# Power-Supplies.net
KiCad netlist of a schematic drawn in Altium Designer
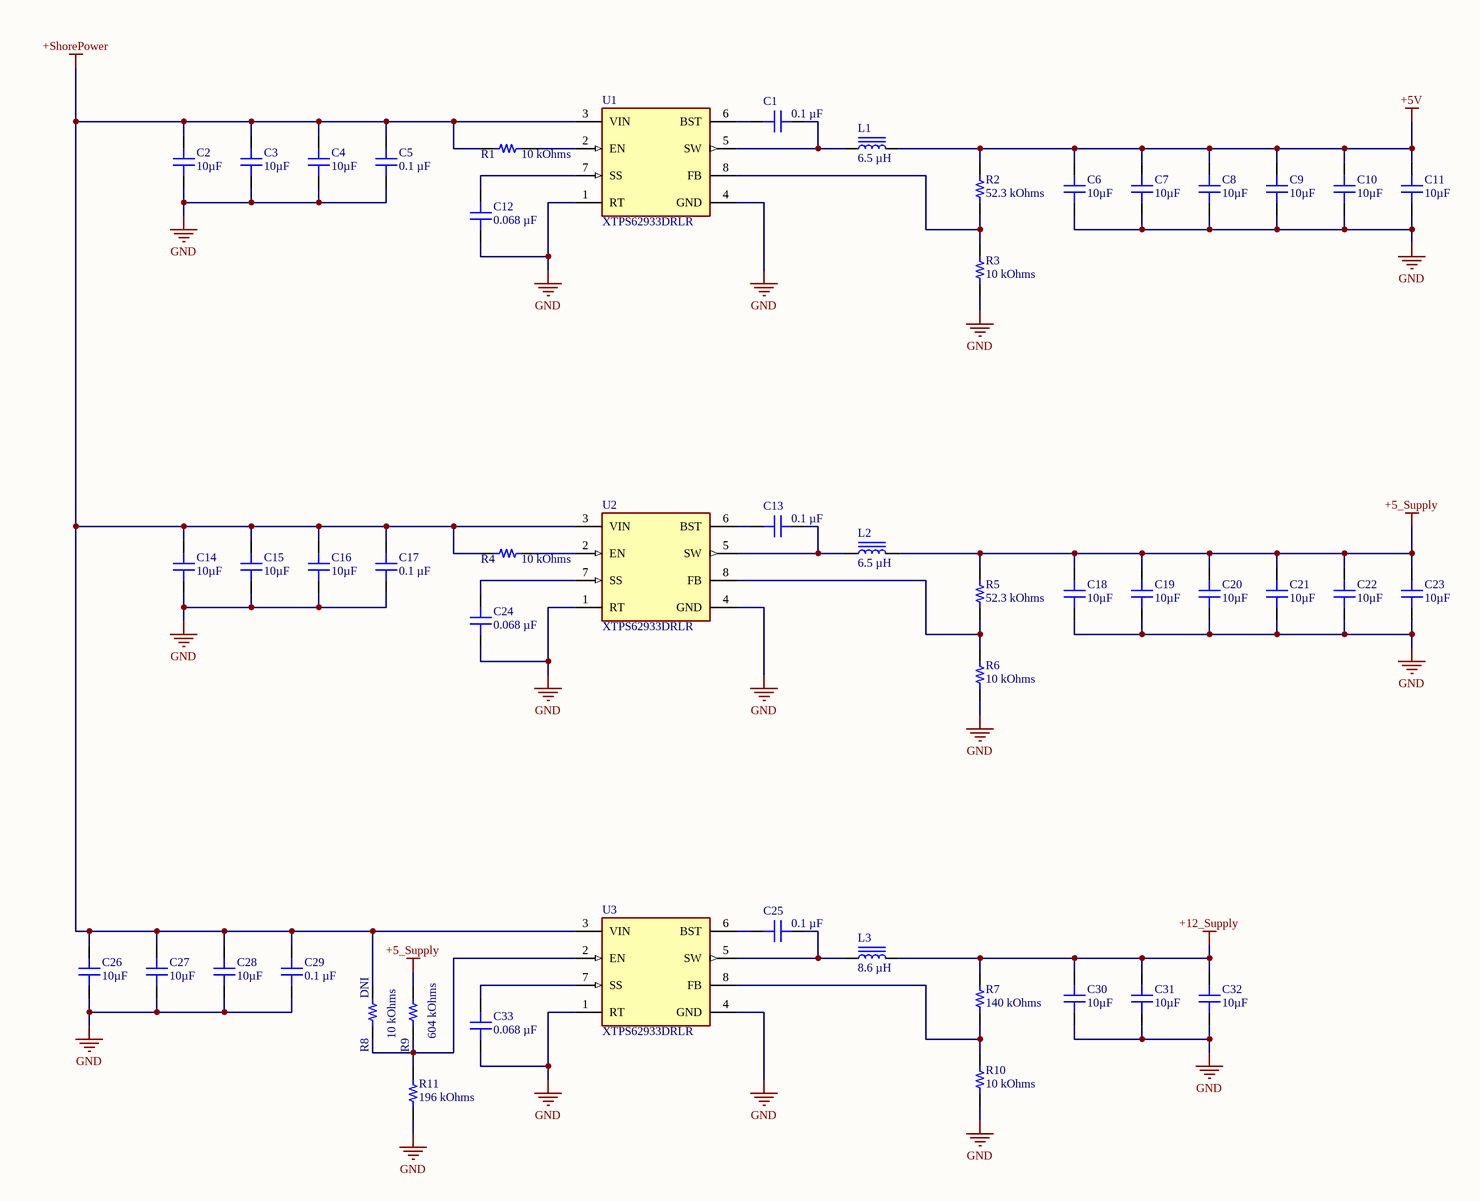
[diagram p0: Power-Supplies.SchDoc]

(export (version "E")
  (design (tool "Eeschema 10.0.6"))
  (components
    (comp (ref "C1")
      (value "0.1 µF")
      (footprint "CAP 0603_1608")
      (description "CAP CER 0.1UF 50V X7R 0603")
      (fields
        (field (name "PART NUMBER") "CL10B104KB8NNWC")
        (field (name "MANUFACTURER") "Samsung Electro-Mechanics")
      )
      (libsource (lib "Celestial Altium Library - altium_library") (part "Capacitor"))
    )
    (comp (ref "C2")
      (value "10µF")
      (footprint "CAP 0805_2012")
      (description "CAP CER 10UF 16V X5R 0805")
      (fields (field (name "PART NUMBER") "CC0805KKX5R7BB106") (field (name "MANUFACTURER") "Yageo"))
      (libsource (lib "Celestial Altium Library - altium_library") (part "Capacitor"))
    )
    (comp (ref "C3")
      (value "10µF")
      (footprint "CAP 0805_2012")
      (description "CAP CER 10UF 16V X5R 0805")
      (fields (field (name "PART NUMBER") "CC0805KKX5R7BB106") (field (name "MANUFACTURER") "Yageo"))
      (libsource (lib "Celestial Altium Library - altium_library") (part "Capacitor"))
    )
    (comp (ref "C4")
      (value "10µF")
      (footprint "CAP 0805_2012")
      (description "CAP CER 10UF 16V X5R 0805")
      (fields (field (name "PART NUMBER") "CC0805KKX5R7BB106") (field (name "MANUFACTURER") "Yageo"))
      (libsource (lib "Celestial Altium Library - altium_library") (part "Capacitor"))
    )
    (comp (ref "C5")
      (value "0.1 µF")
      (footprint "CAP 0603_1608")
      (description "CAP CER 0.1UF 50V X7R 0603")
      (fields
        (field (name "PART NUMBER") "CL10B104KB8NNWC")
        (field (name "MANUFACTURER") "Samsung Electro-Mechanics")
      )
      (libsource (lib "Celestial Altium Library - altium_library") (part "Capacitor"))
    )
    (comp (ref "C6")
      (value "10µF")
      (footprint "CAP 0805_2012")
      (description "CAP CER 10UF 16V X5R 0805")
      (fields (field (name "PART NUMBER") "CC0805KKX5R7BB106") (field (name "MANUFACTURER") "Yageo"))
      (libsource (lib "Celestial Altium Library - altium_library") (part "Capacitor"))
    )
    (comp (ref "C7")
      (value "10µF")
      (footprint "CAP 0805_2012")
      (description "CAP CER 10UF 16V X5R 0805")
      (fields (field (name "PART NUMBER") "CC0805KKX5R7BB106") (field (name "MANUFACTURER") "Yageo"))
      (libsource (lib "Celestial Altium Library - altium_library") (part "Capacitor"))
    )
    (comp (ref "C8")
      (value "10µF")
      (footprint "CAP 0805_2012")
      (description "CAP CER 10UF 16V X5R 0805")
      (fields (field (name "PART NUMBER") "CC0805KKX5R7BB106") (field (name "MANUFACTURER") "Yageo"))
      (libsource (lib "Celestial Altium Library - altium_library") (part "Capacitor"))
    )
    (comp (ref "C9")
      (value "10µF")
      (footprint "CAP 0805_2012")
      (description "CAP CER 10UF 16V X5R 0805")
      (fields (field (name "PART NUMBER") "CC0805KKX5R7BB106") (field (name "MANUFACTURER") "Yageo"))
      (libsource (lib "Celestial Altium Library - altium_library") (part "Capacitor"))
    )
    (comp (ref "C10")
      (value "10µF")
      (footprint "CAP 0805_2012")
      (description "CAP CER 10UF 16V X5R 0805")
      (fields (field (name "PART NUMBER") "CC0805KKX5R7BB106") (field (name "MANUFACTURER") "Yageo"))
      (libsource (lib "Celestial Altium Library - altium_library") (part "Capacitor"))
    )
    (comp (ref "C11")
      (value "10µF")
      (footprint "CAP 0805_2012")
      (description "CAP CER 10UF 16V X5R 0805")
      (fields (field (name "PART NUMBER") "CC0805KKX5R7BB106") (field (name "MANUFACTURER") "Yageo"))
      (libsource (lib "Celestial Altium Library - altium_library") (part "Capacitor"))
    )
    (comp (ref "C12")
      (value "0.068 µF")
      (footprint "CAP 0603_1608")
      (description "CAP CER 0.068UF 25V X7R 0603")
      (fields (field (name "PART NUMBER") "CC0603KRX7R8BB683") (field (name "MANUFACTURER") "Yageo"))
      (libsource (lib "Celestial Altium Library - altium_library") (part "Capacitor"))
    )
    (comp (ref "C13")
      (value "0.1 µF")
      (footprint "CAP 0603_1608")
      (description "CAP CER 0.1UF 50V X7R 0603")
      (fields
        (field (name "PART NUMBER") "CL10B104KB8NNWC")
        (field (name "MANUFACTURER") "Samsung Electro-Mechanics")
      )
      (libsource (lib "Celestial Altium Library - altium_library") (part "Capacitor"))
    )
    (comp (ref "C14")
      (value "10µF")
      (footprint "CAP 0805_2012")
      (description "CAP CER 10UF 16V X5R 0805")
      (fields (field (name "PART NUMBER") "CC0805KKX5R7BB106") (field (name "MANUFACTURER") "Yageo"))
      (libsource (lib "Celestial Altium Library - altium_library") (part "Capacitor"))
    )
    (comp (ref "C15")
      (value "10µF")
      (footprint "CAP 0805_2012")
      (description "CAP CER 10UF 16V X5R 0805")
      (fields (field (name "PART NUMBER") "CC0805KKX5R7BB106") (field (name "MANUFACTURER") "Yageo"))
      (libsource (lib "Celestial Altium Library - altium_library") (part "Capacitor"))
    )
    (comp (ref "C16")
      (value "10µF")
      (footprint "CAP 0805_2012")
      (description "CAP CER 10UF 16V X5R 0805")
      (fields (field (name "PART NUMBER") "CC0805KKX5R7BB106") (field (name "MANUFACTURER") "Yageo"))
      (libsource (lib "Celestial Altium Library - altium_library") (part "Capacitor"))
    )
    (comp (ref "C17")
      (value "0.1 µF")
      (footprint "CAP 0603_1608")
      (description "CAP CER 0.1UF 50V X7R 0603")
      (fields
        (field (name "PART NUMBER") "CL10B104KB8NNWC")
        (field (name "MANUFACTURER") "Samsung Electro-Mechanics")
      )
      (libsource (lib "Celestial Altium Library - altium_library") (part "Capacitor"))
    )
    (comp (ref "C18")
      (value "10µF")
      (footprint "CAP 0805_2012")
      (description "CAP CER 10UF 16V X5R 0805")
      (fields (field (name "PART NUMBER") "CC0805KKX5R7BB106") (field (name "MANUFACTURER") "Yageo"))
      (libsource (lib "Celestial Altium Library - altium_library") (part "Capacitor"))
    )
    (comp (ref "C19")
      (value "10µF")
      (footprint "CAP 0805_2012")
      (description "CAP CER 10UF 16V X5R 0805")
      (fields (field (name "PART NUMBER") "CC0805KKX5R7BB106") (field (name "MANUFACTURER") "Yageo"))
      (libsource (lib "Celestial Altium Library - altium_library") (part "Capacitor"))
    )
    (comp (ref "C20")
      (value "10µF")
      (footprint "CAP 0805_2012")
      (description "CAP CER 10UF 16V X5R 0805")
      (fields (field (name "PART NUMBER") "CC0805KKX5R7BB106") (field (name "MANUFACTURER") "Yageo"))
      (libsource (lib "Celestial Altium Library - altium_library") (part "Capacitor"))
    )
    (comp (ref "C21")
      (value "10µF")
      (footprint "CAP 0805_2012")
      (description "CAP CER 10UF 16V X5R 0805")
      (fields (field (name "PART NUMBER") "CC0805KKX5R7BB106") (field (name "MANUFACTURER") "Yageo"))
      (libsource (lib "Celestial Altium Library - altium_library") (part "Capacitor"))
    )
    (comp (ref "C22")
      (value "10µF")
      (footprint "CAP 0805_2012")
      (description "CAP CER 10UF 16V X5R 0805")
      (fields (field (name "PART NUMBER") "CC0805KKX5R7BB106") (field (name "MANUFACTURER") "Yageo"))
      (libsource (lib "Celestial Altium Library - altium_library") (part "Capacitor"))
    )
    (comp (ref "C23")
      (value "10µF")
      (footprint "CAP 0805_2012")
      (description "CAP CER 10UF 16V X5R 0805")
      (fields (field (name "PART NUMBER") "CC0805KKX5R7BB106") (field (name "MANUFACTURER") "Yageo"))
      (libsource (lib "Celestial Altium Library - altium_library") (part "Capacitor"))
    )
    (comp (ref "C24")
      (value "0.068 µF")
      (footprint "CAP 0603_1608")
      (description "CAP CER 0.068UF 25V X7R 0603")
      (fields (field (name "PART NUMBER") "CC0603KRX7R8BB683") (field (name "MANUFACTURER") "Yageo"))
      (libsource (lib "Celestial Altium Library - altium_library") (part "Capacitor"))
    )
    (comp (ref "C25")
      (value "0.1 µF")
      (footprint "CAP 0603_1608")
      (description "CAP CER 0.1UF 50V X7R 0603")
      (fields
        (field (name "PART NUMBER") "CL10B104KB8NNWC")
        (field (name "MANUFACTURER") "Samsung Electro-Mechanics")
      )
      (libsource (lib "Celestial Altium Library - altium_library") (part "Capacitor"))
    )
    (comp (ref "C26")
      (value "10µF")
      (footprint "CAP 0805_2012")
      (description "CAP CER 10UF 16V X5R 0805")
      (fields (field (name "PART NUMBER") "CC0805KKX5R7BB106") (field (name "MANUFACTURER") "Yageo"))
      (libsource (lib "Celestial Altium Library - altium_library") (part "Capacitor"))
    )
    (comp (ref "C27")
      (value "10µF")
      (footprint "CAP 0805_2012")
      (description "CAP CER 10UF 16V X5R 0805")
      (fields (field (name "PART NUMBER") "CC0805KKX5R7BB106") (field (name "MANUFACTURER") "Yageo"))
      (libsource (lib "Celestial Altium Library - altium_library") (part "Capacitor"))
    )
    (comp (ref "C28")
      (value "10µF")
      (footprint "CAP 0805_2012")
      (description "CAP CER 10UF 16V X5R 0805")
      (fields (field (name "PART NUMBER") "CC0805KKX5R7BB106") (field (name "MANUFACTURER") "Yageo"))
      (libsource (lib "Celestial Altium Library - altium_library") (part "Capacitor"))
    )
    (comp (ref "C29")
      (value "0.1 µF")
      (footprint "CAP 0603_1608")
      (description "CAP CER 0.1UF 50V X7R 0603")
      (fields
        (field (name "PART NUMBER") "CL10B104KB8NNWC")
        (field (name "MANUFACTURER") "Samsung Electro-Mechanics")
      )
      (libsource (lib "Celestial Altium Library - altium_library") (part "Capacitor"))
    )
    (comp (ref "C30")
      (value "10µF")
      (footprint "CAP 0805_2012")
      (description "CAP CER 10UF 16V X5R 0805")
      (fields (field (name "PART NUMBER") "CC0805KKX5R7BB106") (field (name "MANUFACTURER") "Yageo"))
      (libsource (lib "Celestial Altium Library - altium_library") (part "Capacitor"))
    )
    (comp (ref "C31")
      (value "10µF")
      (footprint "CAP 0805_2012")
      (description "CAP CER 10UF 16V X5R 0805")
      (fields (field (name "PART NUMBER") "CC0805KKX5R7BB106") (field (name "MANUFACTURER") "Yageo"))
      (libsource (lib "Celestial Altium Library - altium_library") (part "Capacitor"))
    )
    (comp (ref "C32")
      (value "10µF")
      (footprint "CAP 0805_2012")
      (description "CAP CER 10UF 16V X5R 0805")
      (fields (field (name "PART NUMBER") "CC0805KKX5R7BB106") (field (name "MANUFACTURER") "Yageo"))
      (libsource (lib "Celestial Altium Library - altium_library") (part "Capacitor"))
    )
    (comp (ref "C33")
      (value "0.068 µF")
      (footprint "CAP 0603_1608")
      (description "CAP CER 0.068UF 25V X7R 0603")
      (fields (field (name "PART NUMBER") "CC0603KRX7R8BB683") (field (name "MANUFACTURER") "Yageo"))
      (libsource (lib "Celestial Altium Library - altium_library") (part "Capacitor"))
    )
    (comp (ref "L1")
      (value "6.5 µH")
      (footprint "TAIYO YUDEN NR1005")
      (description "FIXED IND 6.5UH 5.2A 23.4MOHM SM")
      (fields (field (name "PART NUMBER") "NR10050T6R5N") (field (name "MANUFACTURER") "Taiyo Yuden"))
      (libsource (lib "Celestial Altium Library - altium_library") (part "Inductor"))
    )
    (comp (ref "L2")
      (value "6.5 µH")
      (footprint "TAIYO YUDEN NR1005")
      (description "FIXED IND 6.5UH 5.2A 23.4MOHM SM")
      (fields (field (name "PART NUMBER") "NR10050T6R5N") (field (name "MANUFACTURER") "Taiyo Yuden"))
      (libsource (lib "Celestial Altium Library - altium_library") (part "Inductor"))
    )
    (comp (ref "L3")
      (value "8.6 µH")
      (footprint "BOURNS SRR6028")
      (description "FIXED IND 8.6UH 2.1A 56 MOHM SMD")
      (fields (field (name "PART NUMBER") "SRR6028-8R6Y") (field (name "MANUFACTURER") "Bourns Inc."))
      (libsource (lib "Celestial Altium Library - altium_library") (part "Inductor"))
    )
    (comp (ref "R1")
      (value "10 kOhms")
      (footprint "RES 0603_1608")
      (description "RES 10K OHM 5% 1/10W 0603")
      (fields
        (field (name "PART NUMBER") "RMCF0603JT10K0")
        (field (name "MANUFACTURER") "Stackpole Electronics Inc")
      )
      (libsource (lib "Celestial Altium Library - altium_library") (part "Resistor"))
    )
    (comp (ref "R2")
      (value "52.3 kOhms")
      (footprint "RES 0603_1608")
      (description "RES 52.3K OHM 1% 1/10W 0603")
      (fields
        (field (name "PART NUMBER") "RMCF0603FT52K3")
        (field (name "MANUFACTURER") "Stackpole Electronics Inc")
      )
      (libsource (lib "Celestial Altium Library - altium_library") (part "Resistor"))
    )
    (comp (ref "R3")
      (value "10 kOhms")
      (footprint "RES 0603_1608")
      (description "RES 10K OHM 5% 1/10W 0603")
      (fields
        (field (name "PART NUMBER") "RMCF0603JT10K0")
        (field (name "MANUFACTURER") "Stackpole Electronics Inc")
      )
      (libsource (lib "Celestial Altium Library - altium_library") (part "Resistor"))
    )
    (comp (ref "R4")
      (value "10 kOhms")
      (footprint "RES 0603_1608")
      (description "RES 10K OHM 5% 1/10W 0603")
      (fields
        (field (name "PART NUMBER") "RMCF0603JT10K0")
        (field (name "MANUFACTURER") "Stackpole Electronics Inc")
      )
      (libsource (lib "Celestial Altium Library - altium_library") (part "Resistor"))
    )
    (comp (ref "R5")
      (value "52.3 kOhms")
      (footprint "RES 0603_1608")
      (description "RES 52.3K OHM 1% 1/10W 0603")
      (fields
        (field (name "PART NUMBER") "RMCF0603FT52K3")
        (field (name "MANUFACTURER") "Stackpole Electronics Inc")
      )
      (libsource (lib "Celestial Altium Library - altium_library") (part "Resistor"))
    )
    (comp (ref "R6")
      (value "10 kOhms")
      (footprint "RES 0603_1608")
      (description "RES 10K OHM 5% 1/10W 0603")
      (fields
        (field (name "PART NUMBER") "RMCF0603JT10K0")
        (field (name "MANUFACTURER") "Stackpole Electronics Inc")
      )
      (libsource (lib "Celestial Altium Library - altium_library") (part "Resistor"))
    )
    (comp (ref "R7")
      (value "140 kOhms")
      (footprint "RES 0603_1608")
      (description "RES 140K OHM 1% 1/10W 0603")
      (fields
        (field (name "PART NUMBER") "RMCF0603FT140K")
        (field (name "MANUFACTURER") "Stackpole Electronics Inc")
      )
      (libsource (lib "Celestial Altium Library - altium_library") (part "Resistor"))
    )
    (comp (ref "R8")
      (value "10 kOhms")
      (footprint "RES 0603_1608")
      (description "RES 10K OHM 5% 1/10W 0603")
      (fields
        (field (name "PART NUMBER") "RMCF0603JT10K0")
        (field (name "MANUFACTURER") "Stackpole Electronics Inc")
      )
      (libsource (lib "Celestial Altium Library - altium_library") (part "Resistor"))
    )
    (comp (ref "R9")
      (value "604 kOhms")
      (footprint "RES 0603_1608")
      (description "RES 604K OHM 1% 1/10W 0603")
      (fields
        (field (name "PART NUMBER") "RMCF0603FT604K")
        (field (name "MANUFACTURER") "Stackpole Electronics Inc")
      )
      (libsource (lib "Celestial Altium Library - altium_library") (part "Resistor"))
    )
    (comp (ref "R10")
      (value "10 kOhms")
      (footprint "RES 0603_1608")
      (description "RES 10K OHM 5% 1/10W 0603")
      (fields
        (field (name "PART NUMBER") "RMCF0603JT10K0")
        (field (name "MANUFACTURER") "Stackpole Electronics Inc")
      )
      (libsource (lib "Celestial Altium Library - altium_library") (part "Resistor"))
    )
    (comp (ref "R11")
      (value "196 kOhms")
      (footprint "RES 0603_1608")
      (description "RES 196K OHM 1% 1/10W 0603")
      (fields
        (field (name "PART NUMBER") "RMCF0603FT196K")
        (field (name "MANUFACTURER") "Stackpole Electronics Inc")
      )
      (libsource (lib "Celestial Altium Library - altium_library") (part "Resistor"))
    )
    (comp (ref "U1")
      (value "XTPS62933DRLR")
      (footprint "FP-DRL0008A-MFG")
      (libsource (lib "Altium Content Vault") (part "c26cdf3209e329bb3609450725f4e7d"))
    )
    (comp (ref "U2")
      (value "XTPS62933DRLR")
      (footprint "FP-DRL0008A-MFG")
      (libsource (lib "Altium Content Vault") (part "c26cdf3209e329bb3609450725f4e7d"))
    )
    (comp (ref "U3")
      (value "XTPS62933DRLR")
      (footprint "FP-DRL0008A-MFG")
      (libsource (lib "Altium Content Vault") (part "c26cdf3209e329bb3609450725f4e7d"))
    )
  )
  (nets
    (net (code "1") (name "+5V") (class "Default")
      (node (ref "C10") (pin "2") (pinfunction "2_2") (pintype "passive"))
      (node (ref "C11") (pin "2") (pinfunction "2_2") (pintype "passive"))
      (node (ref "C6") (pin "2") (pinfunction "2_2") (pintype "passive"))
      (node (ref "C7") (pin "2") (pinfunction "2_2") (pintype "passive"))
      (node (ref "C8") (pin "2") (pinfunction "2_2") (pintype "passive"))
      (node (ref "C9") (pin "2") (pinfunction "2_2") (pintype "passive"))
      (node (ref "L1") (pin "2") (pinfunction "2_2") (pintype "passive"))
      (node (ref "R2") (pin "2") (pinfunction "2_2") (pintype "passive"))
    )
    (net (code "2") (name "+5_Supply") (class "Default")
      (node (ref "C18") (pin "2") (pinfunction "2_2") (pintype "passive"))
      (node (ref "C19") (pin "2") (pinfunction "2_2") (pintype "passive"))
      (node (ref "C20") (pin "2") (pinfunction "2_2") (pintype "passive"))
      (node (ref "C21") (pin "2") (pinfunction "2_2") (pintype "passive"))
      (node (ref "C22") (pin "2") (pinfunction "2_2") (pintype "passive"))
      (node (ref "C23") (pin "2") (pinfunction "2_2") (pintype "passive"))
      (node (ref "L2") (pin "2") (pinfunction "2_2") (pintype "passive"))
      (node (ref "R5") (pin "2") (pinfunction "2_2") (pintype "passive"))
      (node (ref "R9") (pin "2") (pinfunction "2_2") (pintype "passive"))
    )
    (net (code "3") (name "+12_Supply") (class "Default")
      (node (ref "C30") (pin "2") (pinfunction "2_2") (pintype "passive"))
      (node (ref "C31") (pin "2") (pinfunction "2_2") (pintype "passive"))
      (node (ref "C32") (pin "2") (pinfunction "2_2") (pintype "passive"))
      (node (ref "L3") (pin "2") (pinfunction "2_2") (pintype "passive"))
      (node (ref "R7") (pin "2") (pinfunction "2_2") (pintype "passive"))
    )
    (net (code "4") (name "+ShorePower") (class "Default")
      (node (ref "C14") (pin "2") (pinfunction "2_2") (pintype "passive"))
      (node (ref "C15") (pin "2") (pinfunction "2_2") (pintype "passive"))
      (node (ref "C16") (pin "2") (pinfunction "2_2") (pintype "passive"))
      (node (ref "C17") (pin "1") (pinfunction "1_1") (pintype "passive"))
      (node (ref "C2") (pin "2") (pinfunction "2_2") (pintype "passive"))
      (node (ref "C26") (pin "2") (pinfunction "2_2") (pintype "passive"))
      (node (ref "C27") (pin "2") (pinfunction "2_2") (pintype "passive"))
      (node (ref "C28") (pin "2") (pinfunction "2_2") (pintype "passive"))
      (node (ref "C29") (pin "1") (pinfunction "1_1") (pintype "passive"))
      (node (ref "C3") (pin "2") (pinfunction "2_2") (pintype "passive"))
      (node (ref "C4") (pin "2") (pinfunction "2_2") (pintype "passive"))
      (node (ref "C5") (pin "1") (pinfunction "1_1") (pintype "passive"))
      (node (ref "R1") (pin "1") (pinfunction "1_1") (pintype "passive"))
      (node (ref "R4") (pin "1") (pinfunction "1_1") (pintype "passive"))
      (node (ref "R8") (pin "2") (pinfunction "2_2") (pintype "passive"))
      (node (ref "U1") (pin "3") (pinfunction "VIN_3") (pintype "power_in"))
      (node (ref "U2") (pin "3") (pinfunction "VIN_3") (pintype "power_in"))
      (node (ref "U3") (pin "3") (pinfunction "VIN_3") (pintype "power_in"))
    )
    (net (code "5") (name "GND") (class "Default")
      (node (ref "C10") (pin "1") (pinfunction "1_1") (pintype "passive"))
      (node (ref "C11") (pin "1") (pinfunction "1_1") (pintype "passive"))
      (node (ref "C12") (pin "1") (pinfunction "1_1") (pintype "passive"))
      (node (ref "C14") (pin "1") (pinfunction "1_1") (pintype "passive"))
      (node (ref "C15") (pin "1") (pinfunction "1_1") (pintype "passive"))
      (node (ref "C16") (pin "1") (pinfunction "1_1") (pintype "passive"))
      (node (ref "C17") (pin "2") (pinfunction "2_2") (pintype "passive"))
      (node (ref "C18") (pin "1") (pinfunction "1_1") (pintype "passive"))
      (node (ref "C19") (pin "1") (pinfunction "1_1") (pintype "passive"))
      (node (ref "C2") (pin "1") (pinfunction "1_1") (pintype "passive"))
      (node (ref "C20") (pin "1") (pinfunction "1_1") (pintype "passive"))
      (node (ref "C21") (pin "1") (pinfunction "1_1") (pintype "passive"))
      (node (ref "C22") (pin "1") (pinfunction "1_1") (pintype "passive"))
      (node (ref "C23") (pin "1") (pinfunction "1_1") (pintype "passive"))
      (node (ref "C24") (pin "1") (pinfunction "1_1") (pintype "passive"))
      (node (ref "C26") (pin "1") (pinfunction "1_1") (pintype "passive"))
      (node (ref "C27") (pin "1") (pinfunction "1_1") (pintype "passive"))
      (node (ref "C28") (pin "1") (pinfunction "1_1") (pintype "passive"))
      (node (ref "C29") (pin "2") (pinfunction "2_2") (pintype "passive"))
      (node (ref "C3") (pin "1") (pinfunction "1_1") (pintype "passive"))
      (node (ref "C30") (pin "1") (pinfunction "1_1") (pintype "passive"))
      (node (ref "C31") (pin "1") (pinfunction "1_1") (pintype "passive"))
      (node (ref "C32") (pin "1") (pinfunction "1_1") (pintype "passive"))
      (node (ref "C33") (pin "1") (pinfunction "1_1") (pintype "passive"))
      (node (ref "C4") (pin "1") (pinfunction "1_1") (pintype "passive"))
      (node (ref "C5") (pin "2") (pinfunction "2_2") (pintype "passive"))
      (node (ref "C6") (pin "1") (pinfunction "1_1") (pintype "passive"))
      (node (ref "C7") (pin "1") (pinfunction "1_1") (pintype "passive"))
      (node (ref "C8") (pin "1") (pinfunction "1_1") (pintype "passive"))
      (node (ref "C9") (pin "1") (pinfunction "1_1") (pintype "passive"))
      (node (ref "R10") (pin "1") (pinfunction "1_1") (pintype "passive"))
      (node (ref "R11") (pin "1") (pinfunction "1_1") (pintype "passive"))
      (node (ref "R3") (pin "1") (pinfunction "1_1") (pintype "passive"))
      (node (ref "R6") (pin "1") (pinfunction "1_1") (pintype "passive"))
      (node (ref "U1") (pin "1") (pinfunction "RT_1") (pintype "passive"))
      (node (ref "U1") (pin "4") (pinfunction "GND_4") (pintype "power_in"))
      (node (ref "U2") (pin "1") (pinfunction "RT_1") (pintype "passive"))
      (node (ref "U2") (pin "4") (pinfunction "GND_4") (pintype "power_in"))
      (node (ref "U3") (pin "1") (pinfunction "RT_1") (pintype "passive"))
      (node (ref "U3") (pin "4") (pinfunction "GND_4") (pintype "power_in"))
    )
    (net (code "6") (name "Net-(U1-BST)") (class "Default")
      (node (ref "C1") (pin "2") (pinfunction "2_2") (pintype "passive"))
      (node (ref "U1") (pin "6") (pinfunction "BST_6") (pintype "passive"))
    )
    (net (code "7") (name "Net-(U1-EN)") (class "Default")
      (node (ref "R1") (pin "2") (pinfunction "2_2") (pintype "passive"))
      (node (ref "U1") (pin "2") (pinfunction "EN_2") (pintype "input"))
    )
    (net (code "8") (name "Net-(U1-FB)") (class "Default")
      (node (ref "R2") (pin "1") (pinfunction "1_1") (pintype "passive"))
      (node (ref "R3") (pin "2") (pinfunction "2_2") (pintype "passive"))
      (node (ref "U1") (pin "8") (pinfunction "FB_8") (pintype "passive"))
    )
    (net (code "9") (name "Net-(U1-SS)") (class "Default")
      (node (ref "C12") (pin "2") (pinfunction "2_2") (pintype "passive"))
      (node (ref "U1") (pin "7") (pinfunction "SS_7") (pintype "input"))
    )
    (net (code "10") (name "Net-(U1-SW)") (class "Default")
      (node (ref "C1") (pin "1") (pinfunction "1_1") (pintype "passive"))
      (node (ref "L1") (pin "1") (pinfunction "1_1") (pintype "passive"))
      (node (ref "U1") (pin "5") (pinfunction "SW_5") (pintype "output"))
    )
    (net (code "11") (name "Net-(U2-BST)") (class "Default")
      (node (ref "C13") (pin "2") (pinfunction "2_2") (pintype "passive"))
      (node (ref "U2") (pin "6") (pinfunction "BST_6") (pintype "passive"))
    )
    (net (code "12") (name "Net-(U2-EN)") (class "Default")
      (node (ref "R4") (pin "2") (pinfunction "2_2") (pintype "passive"))
      (node (ref "U2") (pin "2") (pinfunction "EN_2") (pintype "input"))
    )
    (net (code "13") (name "Net-(U2-FB)") (class "Default")
      (node (ref "R5") (pin "1") (pinfunction "1_1") (pintype "passive"))
      (node (ref "R6") (pin "2") (pinfunction "2_2") (pintype "passive"))
      (node (ref "U2") (pin "8") (pinfunction "FB_8") (pintype "passive"))
    )
    (net (code "14") (name "Net-(U2-SS)") (class "Default")
      (node (ref "C24") (pin "2") (pinfunction "2_2") (pintype "passive"))
      (node (ref "U2") (pin "7") (pinfunction "SS_7") (pintype "input"))
    )
    (net (code "15") (name "Net-(U2-SW)") (class "Default")
      (node (ref "C13") (pin "1") (pinfunction "1_1") (pintype "passive"))
      (node (ref "L2") (pin "1") (pinfunction "1_1") (pintype "passive"))
      (node (ref "U2") (pin "5") (pinfunction "SW_5") (pintype "output"))
    )
    (net (code "16") (name "Net-(U3-BST)") (class "Default")
      (node (ref "C25") (pin "2") (pinfunction "2_2") (pintype "passive"))
      (node (ref "U3") (pin "6") (pinfunction "BST_6") (pintype "passive"))
    )
    (net (code "17") (name "Net-(U3-EN)") (class "Default")
      (node (ref "R11") (pin "2") (pinfunction "2_2") (pintype "passive"))
      (node (ref "R8") (pin "1") (pinfunction "1_1") (pintype "passive"))
      (node (ref "R9") (pin "1") (pinfunction "1_1") (pintype "passive"))
      (node (ref "U3") (pin "2") (pinfunction "EN_2") (pintype "input"))
    )
    (net (code "18") (name "Net-(U3-FB)") (class "Default")
      (node (ref "R10") (pin "2") (pinfunction "2_2") (pintype "passive"))
      (node (ref "R7") (pin "1") (pinfunction "1_1") (pintype "passive"))
      (node (ref "U3") (pin "8") (pinfunction "FB_8") (pintype "passive"))
    )
    (net (code "19") (name "Net-(U3-SS)") (class "Default")
      (node (ref "C33") (pin "2") (pinfunction "2_2") (pintype "passive"))
      (node (ref "U3") (pin "7") (pinfunction "SS_7") (pintype "input"))
    )
    (net (code "20") (name "Net-(U3-SW)") (class "Default")
      (node (ref "C25") (pin "1") (pinfunction "1_1") (pintype "passive"))
      (node (ref "L3") (pin "1") (pinfunction "1_1") (pintype "passive"))
      (node (ref "U3") (pin "5") (pinfunction "SW_5") (pintype "output"))
    )
  )
)
